# USB-PS2_1.net
KiCad netlist of a schematic drawn in Altium Designer
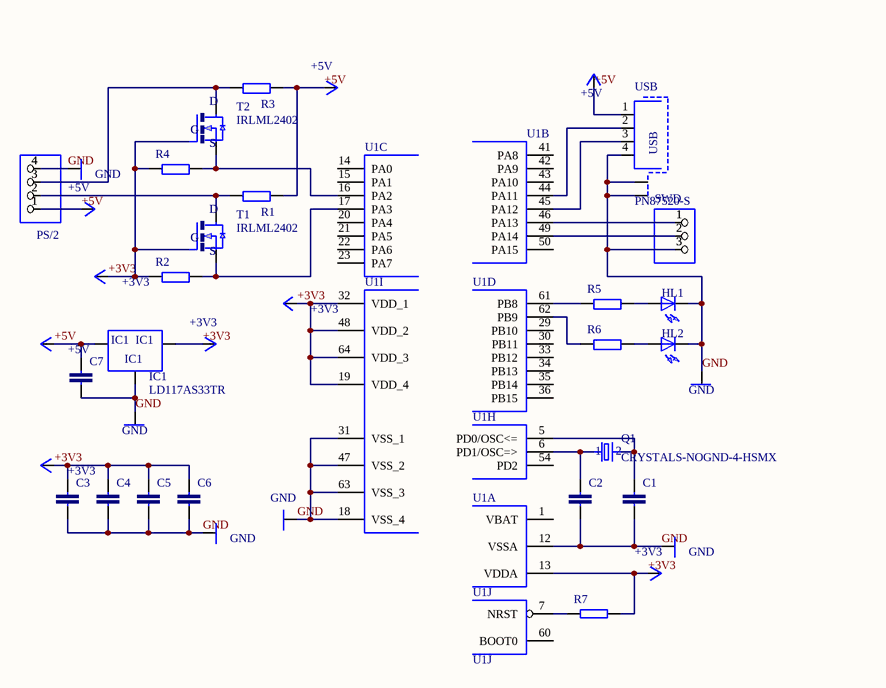
[diagram p0: USB-PS2_1.SchDoc]

(export (version "E")
  (design (tool "Eeschema 10.0.6"))
  (components
    (comp (ref "+3V1") (value "+3V3") (libsource (lib "supply1") (part "+3V3")))
    (comp (ref "+3V2") (value "+3V3") (libsource (lib "supply1") (part "+3V3")))
    (comp (ref "+3V3") (value "+3V3") (libsource (lib "") (part "+3V3_1")))
    (comp (ref "+3V4") (value "+3V3") (libsource (lib "supply1") (part "+3V3")))
    (comp (ref "+3V5") (value "+3V3") (libsource (lib "supply1") (part "+3V3")))
    (comp (ref "C1") (value "~") (footprint "C0603K") (libsource (lib "rcl") (part "C-EUC0603K")))
    (comp (ref "C2") (value "~") (footprint "C0603K") (libsource (lib "rcl") (part "C-EUC0603K")))
    (comp (ref "C3") (value "~") (footprint "C0603K") (libsource (lib "rcl") (part "C-EUC0603K")))
    (comp (ref "C4") (value "~") (footprint "C0603K") (libsource (lib "rcl") (part "C-EUC0603K")))
    (comp (ref "C5") (value "~") (footprint "C0603K") (libsource (lib "rcl") (part "C-EUC0603K")))
    (comp (ref "C6") (value "~") (footprint "C0603K") (libsource (lib "rcl") (part "C-EUC0603K")))
    (comp (ref "C7") (value "~") (footprint "C0603K") (libsource (lib "rcl") (part "C-EUC0603K")))
    (comp (ref "GND1") (value "GND") (libsource (lib "supply1") (part "GND")))
    (comp (ref "GND3") (value "GND") (libsource (lib "") (part "GND_1")))
    (comp (ref "GND4") (value "GND") (libsource (lib "supply1") (part "GND")))
    (comp (ref "GND5") (value "GND") (libsource (lib "supply1") (part "GND")))
    (comp (ref "GND6") (value "GND") (libsource (lib "supply1") (part "GND")))
    (comp (ref "GND7") (value "GND") (libsource (lib "supply1") (part "GND")))
    (comp (ref "HL1") (value "~") (footprint "SML0805") (libsource (lib "led") (part "LEDSML0805")))
    (comp (ref "HL2") (value "~") (footprint "SML0805") (libsource (lib "led") (part "LEDSML0805")))
    (comp (ref "IC1")
      (value "LD117AS33TR")
      (footprint "SOT223")
      (libsource (lib "v-reg") (part "LD117AS33TR"))
    )
    (comp (ref "P+1") (value "+5V") (libsource (lib "") (part "+5V_1")))
    (comp (ref "P+2") (value "+5V") (libsource (lib "") (part "+5V_1")))
    (comp (ref "P+3") (value "+5V") (libsource (lib "") (part "+5V_1")))
    (comp (ref "P+4") (value "+5V") (libsource (lib "supply1") (part "+5V")))
    (comp (ref "PS/2") (value "~") (footprint "1X04") (libsource (lib "pinhead") (part "PINHD-1X4")))
    (comp (ref "Q1")
      (value "CRYSTALS-NOGND-4-HSMX")
      (footprint "HC49-4-HSMX")
      (libsource (lib "IQD-Frequency-Products") (part "CRYSTALS-NOGND-4-HSMX"))
    )
    (comp (ref "R1") (value "~") (footprint "R0603") (libsource (lib "rcl") (part "R-EU_R0603")))
    (comp (ref "R2") (value "~") (footprint "R0603") (libsource (lib "") (part "R-EU_R0603_1")))
    (comp (ref "R3") (value "~") (footprint "R0603") (libsource (lib "rcl") (part "R-EU_R0603")))
    (comp (ref "R4") (value "~") (footprint "R0603") (libsource (lib "") (part "R-EU_R0603_1")))
    (comp (ref "R5") (value "~") (footprint "R0603") (libsource (lib "") (part "R-EU_R0603_1")))
    (comp (ref "R6") (value "~") (footprint "R0603") (libsource (lib "") (part "R-EU_R0603_1")))
    (comp (ref "R7") (value "~") (footprint "R0603") (libsource (lib "") (part "R-EU_R0603_2")))
    (comp (ref "SWD") (value "~") (footprint "1X03") (libsource (lib "pinhead") (part "PINHD-1X3")))
    (comp (ref "T1")
      (value "IRLML2402")
      (footprint "MICRO3")
      (libsource (lib "transistor-power") (part "IRLML2402"))
    )
    (comp (ref "T2")
      (value "IRLML2402")
      (footprint "MICRO3")
      (libsource (lib "transistor-power") (part "IRLML2402"))
    )
    (comp (ref "U1") (value "~") (footprint "TQFP64") (libsource (lib "stm32") (part "STM32F10XRXT6")))
    (comp (ref "USB")
      (value "PN87520-S")
      (footprint "PN87520-S")
      (libsource (lib "con-berg") (part "PN87520-S"))
    )
  )
  (nets
    (net (code "1") (name "/+3V3") (class "Default")
      (node (ref "+3V1") (pin "0") (pinfunction "+3V3_0") (pintype "passive"))
      (node (ref "+3V2") (pin "0") (pinfunction "+3V3_0") (pintype "passive"))
      (node (ref "+3V3") (pin "0") (pinfunction "+3V3_0") (pintype "passive"))
      (node (ref "+3V4") (pin "0") (pinfunction "+3V3_0") (pintype "passive"))
      (node (ref "+3V5") (pin "0") (pinfunction "+3V3_0") (pintype "passive"))
      (node (ref "C3") (pin "1") (pinfunction "1_1") (pintype "passive"))
      (node (ref "C4") (pin "1") (pinfunction "1_1") (pintype "passive"))
      (node (ref "C5") (pin "1") (pinfunction "1_1") (pintype "passive"))
      (node (ref "C6") (pin "1") (pinfunction "1_1") (pintype "passive"))
      (node (ref "IC1") (pin "4") (pinfunction "OUT_4") (pintype "passive"))
      (node (ref "R2") (pin "1") (pinfunction "1_1") (pintype "passive"))
      (node (ref "R4") (pin "1") (pinfunction "1_1") (pintype "passive"))
      (node (ref "R7") (pin "2") (pinfunction "2_2") (pintype "passive"))
      (node (ref "T1") (pin "1") (pinfunction "G_1") (pintype "passive"))
      (node (ref "T2") (pin "1") (pinfunction "G_1") (pintype "passive"))
      (node (ref "U1") (pin "13") (pinfunction "VDDA_13") (pintype "passive"))
      (node (ref "U1") (pin "19") (pinfunction "VDD_4_19") (pintype "passive"))
      (node (ref "U1") (pin "32") (pinfunction "VDD_1_32") (pintype "passive"))
      (node (ref "U1") (pin "48") (pinfunction "VDD_2_48") (pintype "passive"))
      (node (ref "U1") (pin "64") (pinfunction "VDD_3_64") (pintype "passive"))
    )
    (net (code "2") (name "/+5V") (class "Default")
      (node (ref "C7") (pin "1") (pinfunction "1_1") (pintype "passive"))
      (node (ref "IC1") (pin "3") (pinfunction "IN_3") (pintype "passive"))
      (node (ref "P+1") (pin "0") (pinfunction "+5V_0") (pintype "passive"))
      (node (ref "P+2") (pin "0") (pinfunction "+5V_0") (pintype "passive"))
      (node (ref "P+3") (pin "0") (pinfunction "+5V_0") (pintype "passive"))
      (node (ref "P+4") (pin "0") (pinfunction "+5V_0") (pintype "passive"))
      (node (ref "PS/2") (pin "1") (pinfunction "1_1") (pintype "passive"))
      (node (ref "R1") (pin "1") (pinfunction "1_1") (pintype "passive"))
      (node (ref "R3") (pin "1") (pinfunction "1_1") (pintype "passive"))
      (node (ref "USB") (pin "1") (pinfunction "1_1") (pintype "passive"))
    )
    (net (code "3") (name "/GND") (class "Default")
      (node (ref "C1") (pin "2") (pinfunction "2_2") (pintype "passive"))
      (node (ref "C2") (pin "2") (pinfunction "2_2") (pintype "passive"))
      (node (ref "C3") (pin "2") (pinfunction "2_2") (pintype "passive"))
      (node (ref "C4") (pin "2") (pinfunction "2_2") (pintype "passive"))
      (node (ref "C5") (pin "2") (pinfunction "2_2") (pintype "passive"))
      (node (ref "C6") (pin "2") (pinfunction "2_2") (pintype "passive"))
      (node (ref "C7") (pin "2") (pinfunction "2_2") (pintype "passive"))
      (node (ref "GND1") (pin "0") (pinfunction "GND_0") (pintype "passive"))
      (node (ref "GND3") (pin "0") (pinfunction "GND_0") (pintype "passive"))
      (node (ref "GND4") (pin "0") (pinfunction "GND_0") (pintype "passive"))
      (node (ref "GND5") (pin "0") (pinfunction "GND_0") (pintype "passive"))
      (node (ref "GND6") (pin "0") (pinfunction "GND_0") (pintype "passive"))
      (node (ref "GND7") (pin "0") (pinfunction "GND_0") (pintype "passive"))
      (node (ref "HL1") (pin "C") (pinfunction "C_C") (pintype "passive"))
      (node (ref "HL2") (pin "C") (pinfunction "C_C") (pintype "passive"))
      (node (ref "IC1") (pin "1") (pinfunction "ADJ_1") (pintype "passive"))
      (node (ref "PS/2") (pin "4") (pinfunction "4_4") (pintype "passive"))
      (node (ref "SWD") (pin "3") (pinfunction "3_3") (pintype "passive"))
      (node (ref "U1") (pin "12") (pinfunction "VSSA_12") (pintype "passive"))
      (node (ref "U1") (pin "18") (pinfunction "VSS_4_18") (pintype "passive"))
      (node (ref "U1") (pin "31") (pinfunction "VSS_1_31") (pintype "passive"))
      (node (ref "U1") (pin "47") (pinfunction "VSS_2_47") (pintype "passive"))
      (node (ref "U1") (pin "63") (pinfunction "VSS_3_63") (pintype "passive"))
      (node (ref "USB") (pin "4") (pinfunction "4_4") (pintype "passive"))
      (node (ref "USB") (pin "S1") (pinfunction "S1_S1") (pintype "passive"))
      (node (ref "USB") (pin "S2") (pinfunction "S2_S2") (pintype "passive"))
    )
    (net (code "4") (name "Net-(HL1-PadA)") (class "Default")
      (node (ref "HL1") (pin "A") (pinfunction "A_A") (pintype "passive"))
      (node (ref "R5") (pin "2") (pinfunction "2_2") (pintype "passive"))
    )
    (net (code "5") (name "Net-(HL2-PadA)") (class "Default")
      (node (ref "HL2") (pin "A") (pinfunction "A_A") (pintype "passive"))
      (node (ref "R6") (pin "2") (pinfunction "2_2") (pintype "passive"))
    )
    (net (code "6") (name "Net-(T1-D)") (class "Default")
      (node (ref "PS/2") (pin "2") (pinfunction "2_2") (pintype "passive"))
      (node (ref "R1") (pin "2") (pinfunction "2_2") (pintype "passive"))
      (node (ref "T1") (pin "3") (pinfunction "D_3") (pintype "passive"))
    )
    (net (code "7") (name "Net-(T1-S)") (class "Default")
      (node (ref "R2") (pin "2") (pinfunction "2_2") (pintype "passive"))
      (node (ref "T1") (pin "2") (pinfunction "S_2") (pintype "passive"))
      (node (ref "U1") (pin "17") (pinfunction "PA3_17") (pintype "passive"))
    )
    (net (code "8") (name "Net-(T2-D)") (class "Default")
      (node (ref "PS/2") (pin "3") (pinfunction "3_3") (pintype "passive"))
      (node (ref "R3") (pin "2") (pinfunction "2_2") (pintype "passive"))
      (node (ref "T2") (pin "3") (pinfunction "D_3") (pintype "passive"))
    )
    (net (code "9") (name "Net-(T2-S)") (class "Default")
      (node (ref "R4") (pin "2") (pinfunction "2_2") (pintype "passive"))
      (node (ref "T2") (pin "2") (pinfunction "S_2") (pintype "passive"))
      (node (ref "U1") (pin "16") (pinfunction "PA2_16") (pintype "passive"))
    )
    (net (code "10") (name "Net-(U1B-PA11)") (class "Default")
      (node (ref "U1") (pin "44") (pinfunction "PA11_44") (pintype "passive"))
      (node (ref "USB") (pin "2") (pinfunction "2_2") (pintype "passive"))
    )
    (net (code "11") (name "Net-(U1B-PA12)") (class "Default")
      (node (ref "U1") (pin "45") (pinfunction "PA12_45") (pintype "passive"))
      (node (ref "USB") (pin "3") (pinfunction "3_3") (pintype "passive"))
    )
    (net (code "12") (name "Net-(U1B-PA13)") (class "Default")
      (node (ref "SWD") (pin "1") (pinfunction "1_1") (pintype "passive"))
      (node (ref "U1") (pin "46") (pinfunction "PA13_46") (pintype "passive"))
    )
    (net (code "13") (name "Net-(U1B-PA14)") (class "Default")
      (node (ref "SWD") (pin "2") (pinfunction "2_2") (pintype "passive"))
      (node (ref "U1") (pin "49") (pinfunction "PA14_49") (pintype "passive"))
    )
    (net (code "14") (name "Net-(U1D-PB8)") (class "Default")
      (node (ref "R5") (pin "1") (pinfunction "1_1") (pintype "passive"))
      (node (ref "U1") (pin "61") (pinfunction "PB8_61") (pintype "passive"))
    )
    (net (code "15") (name "Net-(U1D-PB9)") (class "Default")
      (node (ref "R6") (pin "1") (pinfunction "1_1") (pintype "passive"))
      (node (ref "U1") (pin "62") (pinfunction "PB9_62") (pintype "passive"))
    )
    (net (code "16") (name "Net-(U1H-PD0{slash}OSC<=)") (class "Default")
      (node (ref "C1") (pin "1") (pinfunction "1_1") (pintype "passive"))
      (node (ref "Q1") (pin "2") (pinfunction "2_2") (pintype "passive"))
      (node (ref "U1") (pin "5") (pinfunction "PD0/OSC<=_5") (pintype "passive"))
    )
    (net (code "17") (name "Net-(U1H-PD1{slash}OSC=>)") (class "Default")
      (node (ref "C2") (pin "1") (pinfunction "1_1") (pintype "passive"))
      (node (ref "Q1") (pin "1") (pinfunction "1_1") (pintype "passive"))
      (node (ref "U1") (pin "6") (pinfunction "PD1/OSC=>_6") (pintype "passive"))
    )
    (net (code "18") (name "Net-(U1J-NRST)") (class "Default")
      (node (ref "R7") (pin "1") (pinfunction "1_1") (pintype "passive"))
      (node (ref "U1") (pin "7") (pinfunction "NRST_7") (pintype "passive"))
    )
    (net (code "19") (name "unconnected-(U1A-VBAT-Pad1)") (class "Default")
      (node (ref "U1") (pin "1") (pinfunction "VBAT_1") (pintype "passive"))
    )
    (net (code "20") (name "unconnected-(U1B-PA8-Pad41)") (class "Default")
      (node (ref "U1") (pin "41") (pinfunction "PA8_41") (pintype "passive"))
    )
    (net (code "21") (name "unconnected-(U1B-PA9-Pad42)") (class "Default")
      (node (ref "U1") (pin "42") (pinfunction "PA9_42") (pintype "passive"))
    )
    (net (code "22") (name "unconnected-(U1B-PA10-Pad43)") (class "Default")
      (node (ref "U1") (pin "43") (pinfunction "PA10_43") (pintype "passive"))
    )
    (net (code "23") (name "unconnected-(U1B-PA15-Pad50)") (class "Default")
      (node (ref "U1") (pin "50") (pinfunction "PA15_50") (pintype "passive"))
    )
    (net (code "24") (name "unconnected-(U1C-PA0-Pad14)") (class "Default")
      (node (ref "U1") (pin "14") (pinfunction "PA0_14") (pintype "passive"))
    )
    (net (code "25") (name "unconnected-(U1C-PA1-Pad15)") (class "Default")
      (node (ref "U1") (pin "15") (pinfunction "PA1_15") (pintype "passive"))
    )
    (net (code "26") (name "unconnected-(U1C-PA4-Pad20)") (class "Default")
      (node (ref "U1") (pin "20") (pinfunction "PA4_20") (pintype "passive"))
    )
    (net (code "27") (name "unconnected-(U1C-PA5-Pad21)") (class "Default")
      (node (ref "U1") (pin "21") (pinfunction "PA5_21") (pintype "passive"))
    )
    (net (code "28") (name "unconnected-(U1C-PA6-Pad22)") (class "Default")
      (node (ref "U1") (pin "22") (pinfunction "PA6_22") (pintype "passive"))
    )
    (net (code "29") (name "unconnected-(U1C-PA7-Pad23)") (class "Default")
      (node (ref "U1") (pin "23") (pinfunction "PA7_23") (pintype "passive"))
    )
    (net (code "30") (name "unconnected-(U1D-PB10-Pad29)") (class "Default")
      (node (ref "U1") (pin "29") (pinfunction "PB10_29") (pintype "passive"))
    )
    (net (code "31") (name "unconnected-(U1D-PB11-Pad30)") (class "Default")
      (node (ref "U1") (pin "30") (pinfunction "PB11_30") (pintype "passive"))
    )
    (net (code "32") (name "unconnected-(U1D-PB12-Pad33)") (class "Default")
      (node (ref "U1") (pin "33") (pinfunction "PB12_33") (pintype "passive"))
    )
    (net (code "33") (name "unconnected-(U1D-PB13-Pad34)") (class "Default")
      (node (ref "U1") (pin "34") (pinfunction "PB13_34") (pintype "passive"))
    )
    (net (code "34") (name "unconnected-(U1D-PB14-Pad35)") (class "Default")
      (node (ref "U1") (pin "35") (pinfunction "PB14_35") (pintype "passive"))
    )
    (net (code "35") (name "unconnected-(U1D-PB15-Pad36)") (class "Default")
      (node (ref "U1") (pin "36") (pinfunction "PB15_36") (pintype "passive"))
    )
    (net (code "36") (name "unconnected-(U1H-PD2-Pad54)") (class "Default")
      (node (ref "U1") (pin "54") (pinfunction "PD2_54") (pintype "passive"))
    )
    (net (code "37") (name "unconnected-(U1J-BOOT0-Pad60)") (class "Default")
      (node (ref "U1") (pin "60") (pinfunction "BOOT0_60") (pintype "passive"))
    )
  )
)
